# Uloha1.net
KiCad netlist of a schematic drawn in EAGLE
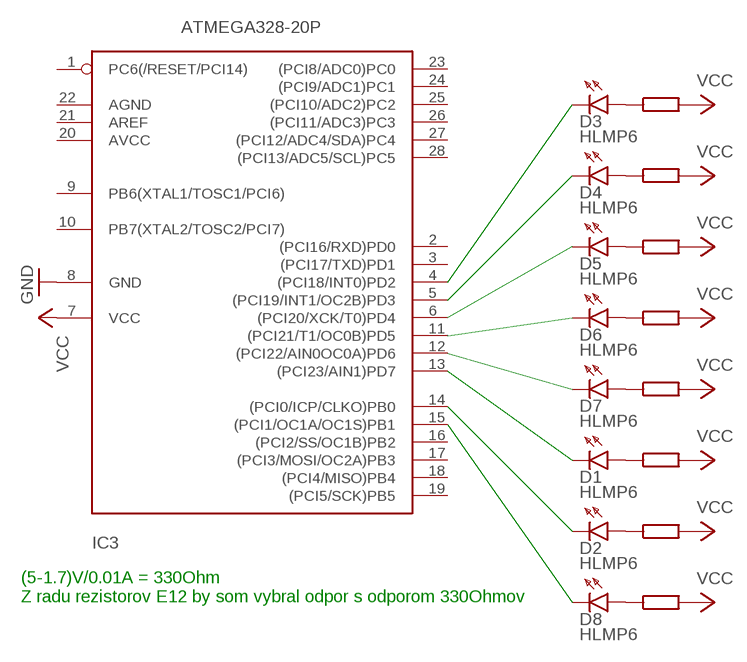
[diagram p0: schematic, sheet 1]

(export (version "E")
  (design (tool "Eeschema 10.0.6"))
  (components
    (comp (ref "D1")
      (value "HLMP6")
      (footprint "eagle-import:HLMP6")
      (fields (field (name "MF") "AGILENT TECHNOLOGIES") (field (name "MPN") "HLMP-6500"))
      (libsource (lib "eagle-import") (part "HLMP6"))
    )
    (comp (ref "D2")
      (value "HLMP6")
      (footprint "eagle-import:HLMP6")
      (fields (field (name "MF") "AGILENT TECHNOLOGIES") (field (name "MPN") "HLMP-6500"))
      (libsource (lib "eagle-import") (part "HLMP6"))
    )
    (comp (ref "D3")
      (value "HLMP6")
      (footprint "eagle-import:HLMP6")
      (fields (field (name "MF") "AGILENT TECHNOLOGIES") (field (name "MPN") "HLMP-6500"))
      (libsource (lib "eagle-import") (part "HLMP6"))
    )
    (comp (ref "D4")
      (value "HLMP6")
      (footprint "eagle-import:HLMP6")
      (fields (field (name "MF") "AGILENT TECHNOLOGIES") (field (name "MPN") "HLMP-6500"))
      (libsource (lib "eagle-import") (part "HLMP6"))
    )
    (comp (ref "D5")
      (value "HLMP6")
      (footprint "eagle-import:HLMP6")
      (fields (field (name "MF") "AGILENT TECHNOLOGIES") (field (name "MPN") "HLMP-6500"))
      (libsource (lib "eagle-import") (part "HLMP6"))
    )
    (comp (ref "D6")
      (value "HLMP6")
      (footprint "eagle-import:HLMP6")
      (fields (field (name "MF") "AGILENT TECHNOLOGIES") (field (name "MPN") "HLMP-6500"))
      (libsource (lib "eagle-import") (part "HLMP6"))
    )
    (comp (ref "D7")
      (value "HLMP6")
      (footprint "eagle-import:HLMP6")
      (fields (field (name "MF") "AGILENT TECHNOLOGIES") (field (name "MPN") "HLMP-6500"))
      (libsource (lib "eagle-import") (part "HLMP6"))
    )
    (comp (ref "D8")
      (value "HLMP6")
      (footprint "eagle-import:HLMP6")
      (fields (field (name "MF") "AGILENT TECHNOLOGIES") (field (name "MPN") "HLMP-6500"))
      (libsource (lib "eagle-import") (part "HLMP6"))
    )
    (comp (ref "IC3")
      (value "ATMEGA328-20P")
      (footprint "eagle-import:DIL28-3")
      (libsource (lib "eagle-import") (part "ATMEGA328P-20"))
    )
  )
  (nets
    (net (code "1") (name "GND") (class "Default")
      (node (ref "IC3") (pin "8") (pinfunction "GND_8") (pintype "bidirectional"))
    )
    (net (code "2") (name "Net-(IC3-(PCI0{slash}ICP{slash}CLKO)PB0)") (class "Default")
      (node (ref "D2") (pin "K") (pinfunction "K_K") (pintype "passive"))
      (node (ref "IC3") (pin "14") (pinfunction "(PCI0/ICP/CLKO)PB0_14") (pintype "bidirectional"))
    )
    (net (code "3") (name "Net-(IC3-(PCI1{slash}OC1A{slash}OC1S)PB1)") (class "Default")
      (node (ref "D8") (pin "K") (pinfunction "K_K") (pintype "passive"))
      (node (ref "IC3") (pin "15") (pinfunction "(PCI1/OC1A/OC1S)PB1_15") (pintype "bidirectional"))
    )
    (net (code "4") (name "Net-(IC3-(PCI18{slash}INT0)PD2)") (class "Default")
      (node (ref "D3") (pin "K") (pinfunction "K_K") (pintype "passive"))
      (node (ref "IC3") (pin "4") (pinfunction "(PCI18/INT0)PD2_4") (pintype "bidirectional"))
    )
    (net (code "5") (name "Net-(IC3-(PCI19{slash}INT1{slash}OC2B)PD3)") (class "Default")
      (node (ref "D4") (pin "K") (pinfunction "K_K") (pintype "passive"))
      (node (ref "IC3") (pin "5") (pinfunction "(PCI19/INT1/OC2B)PD3_5") (pintype "bidirectional"))
    )
    (net (code "6") (name "Net-(IC3-(PCI20{slash}XCK{slash}T0)PD4)") (class "Default")
      (node (ref "D5") (pin "K") (pinfunction "K_K") (pintype "passive"))
      (node (ref "IC3") (pin "6") (pinfunction "(PCI20/XCK/T0)PD4_6") (pintype "bidirectional"))
    )
    (net (code "7") (name "Net-(IC3-(PCI21{slash}T1{slash}OC0B)PD5)") (class "Default")
      (node (ref "D6") (pin "K") (pinfunction "K_K") (pintype "passive"))
      (node (ref "IC3") (pin "11") (pinfunction "(PCI21/T1/OC0B)PD5_11") (pintype "bidirectional"))
    )
    (net (code "8") (name "Net-(IC3-(PCI22{slash}AIN0OC0A)PD6)") (class "Default")
      (node (ref "D7") (pin "K") (pinfunction "K_K") (pintype "passive"))
      (node (ref "IC3") (pin "12") (pinfunction "(PCI22/AIN0OC0A)PD6_12") (pintype "bidirectional"))
    )
    (net (code "9") (name "Net-(IC3-(PCI23{slash}AIN1)PD7)") (class "Default")
      (node (ref "D1") (pin "K") (pinfunction "K_K") (pintype "passive"))
      (node (ref "IC3") (pin "13") (pinfunction "(PCI23/AIN1)PD7_13") (pintype "bidirectional"))
    )
    (net (code "10") (name "VCC") (class "Default")
      (node (ref "IC3") (pin "7") (pinfunction "VCC_7") (pintype "bidirectional"))
    )
    (net (code "11") (name "unconnected-(D1-PadA)") (class "Default")
      (node (ref "D1") (pin "A") (pinfunction "A_A") (pintype "passive"))
    )
    (net (code "12") (name "unconnected-(D2-PadA)") (class "Default")
      (node (ref "D2") (pin "A") (pinfunction "A_A") (pintype "passive"))
    )
    (net (code "13") (name "unconnected-(D3-PadA)") (class "Default")
      (node (ref "D3") (pin "A") (pinfunction "A_A") (pintype "passive"))
    )
    (net (code "14") (name "unconnected-(D4-PadA)") (class "Default")
      (node (ref "D4") (pin "A") (pinfunction "A_A") (pintype "passive"))
    )
    (net (code "15") (name "unconnected-(D5-PadA)") (class "Default")
      (node (ref "D5") (pin "A") (pinfunction "A_A") (pintype "passive"))
    )
    (net (code "16") (name "unconnected-(D6-PadA)") (class "Default")
      (node (ref "D6") (pin "A") (pinfunction "A_A") (pintype "passive"))
    )
    (net (code "17") (name "unconnected-(D7-PadA)") (class "Default")
      (node (ref "D7") (pin "A") (pinfunction "A_A") (pintype "passive"))
    )
    (net (code "18") (name "unconnected-(D8-PadA)") (class "Default")
      (node (ref "D8") (pin "A") (pinfunction "A_A") (pintype "passive"))
    )
    (net (code "19") (name "unconnected-(IC3-(PCI2{slash}SS{slash}OC1B)PB2-Pad16)") (class "Default")
      (node (ref "IC3") (pin "16") (pinfunction "(PCI2/SS/OC1B)PB2_16") (pintype "bidirectional"))
    )
    (net (code "20") (name "unconnected-(IC3-(PCI3{slash}MOSI{slash}OC2A)PB3-Pad17)") (class "Default")
      (node (ref "IC3") (pin "17") (pinfunction "(PCI3/MOSI/OC2A)PB3_17") (pintype "bidirectional"))
    )
    (net (code "21") (name "unconnected-(IC3-(PCI4{slash}MISO)PB4-Pad18)") (class "Default")
      (node (ref "IC3") (pin "18") (pinfunction "(PCI4/MISO)PB4_18") (pintype "bidirectional"))
    )
    (net (code "22") (name "unconnected-(IC3-(PCI5{slash}SCK)PB5-Pad19)") (class "Default")
      (node (ref "IC3") (pin "19") (pinfunction "(PCI5/SCK)PB5_19") (pintype "bidirectional"))
    )
    (net (code "23") (name "unconnected-(IC3-(PCI8{slash}ADC0)PC0-Pad23)") (class "Default")
      (node (ref "IC3") (pin "23") (pinfunction "(PCI8/ADC0)PC0_23") (pintype "bidirectional"))
    )
    (net (code "24") (name "unconnected-(IC3-(PCI9{slash}ADC1)PC1-Pad24)") (class "Default")
      (node (ref "IC3") (pin "24") (pinfunction "(PCI9/ADC1)PC1_24") (pintype "bidirectional"))
    )
    (net (code "25") (name "unconnected-(IC3-(PCI10{slash}ADC2)PC2-Pad25)") (class "Default")
      (node (ref "IC3") (pin "25") (pinfunction "(PCI10/ADC2)PC2_25") (pintype "bidirectional"))
    )
    (net (code "26") (name "unconnected-(IC3-(PCI11{slash}ADC3)PC3-Pad26)") (class "Default")
      (node (ref "IC3") (pin "26") (pinfunction "(PCI11/ADC3)PC3_26") (pintype "bidirectional"))
    )
    (net (code "27") (name "unconnected-(IC3-(PCI12{slash}ADC4{slash}SDA)PC4-Pad27)") (class "Default")
      (node (ref "IC3") (pin "27") (pinfunction "(PCI12/ADC4/SDA)PC4_27") (pintype "bidirectional"))
    )
    (net (code "28") (name "unconnected-(IC3-(PCI13{slash}ADC5{slash}SCL)PC5-Pad28)") (class "Default")
      (node (ref "IC3") (pin "28") (pinfunction "(PCI13/ADC5/SCL)PC5_28") (pintype "bidirectional"))
    )
    (net (code "29") (name "unconnected-(IC3-(PCI16{slash}RXD)PD0-Pad2)") (class "Default")
      (node (ref "IC3") (pin "2") (pinfunction "(PCI16/RXD)PD0_2") (pintype "bidirectional"))
    )
    (net (code "30") (name "unconnected-(IC3-(PCI17{slash}TXD)PD1-Pad3)") (class "Default")
      (node (ref "IC3") (pin "3") (pinfunction "(PCI17/TXD)PD1_3") (pintype "bidirectional"))
    )
    (net (code "31") (name "unconnected-(IC3-AGND-Pad22)") (class "Default")
      (node (ref "IC3") (pin "22") (pinfunction "AGND_22") (pintype "bidirectional"))
    )
    (net (code "32") (name "unconnected-(IC3-AREF-Pad21)") (class "Default")
      (node (ref "IC3") (pin "21") (pinfunction "AREF_21") (pintype "bidirectional"))
    )
    (net (code "33") (name "unconnected-(IC3-AVCC-Pad20)") (class "Default")
      (node (ref "IC3") (pin "20") (pinfunction "AVCC_20") (pintype "bidirectional"))
    )
    (net (code "34") (name "unconnected-(IC3-PB6(XTAL1{slash}TOSC1{slash}PCI6)-Pad9)") (class "Default")
      (node (ref "IC3") (pin "9") (pinfunction "PB6(XTAL1/TOSC1/PCI6)_9") (pintype "bidirectional"))
    )
    (net (code "35") (name "unconnected-(IC3-PB7(XTAL2{slash}TOSC2{slash}PCI7)-Pad10)") (class "Default")
      (node (ref "IC3") (pin "10") (pinfunction "PB7(XTAL2/TOSC2/PCI7)_10") (pintype "bidirectional"))
    )
    (net (code "36") (name "unconnected-(IC3-PC6({slash}RESET{slash}PCI14)-Pad1)") (class "Default")
      (node (ref "IC3") (pin "1") (pinfunction "PC6(/RESET/PCI14)_1") (pintype "bidirectional"))
    )
  )
)
